# AstroEQ_PTH_V4_7.net
KiCad netlist of a schematic drawn in EAGLE
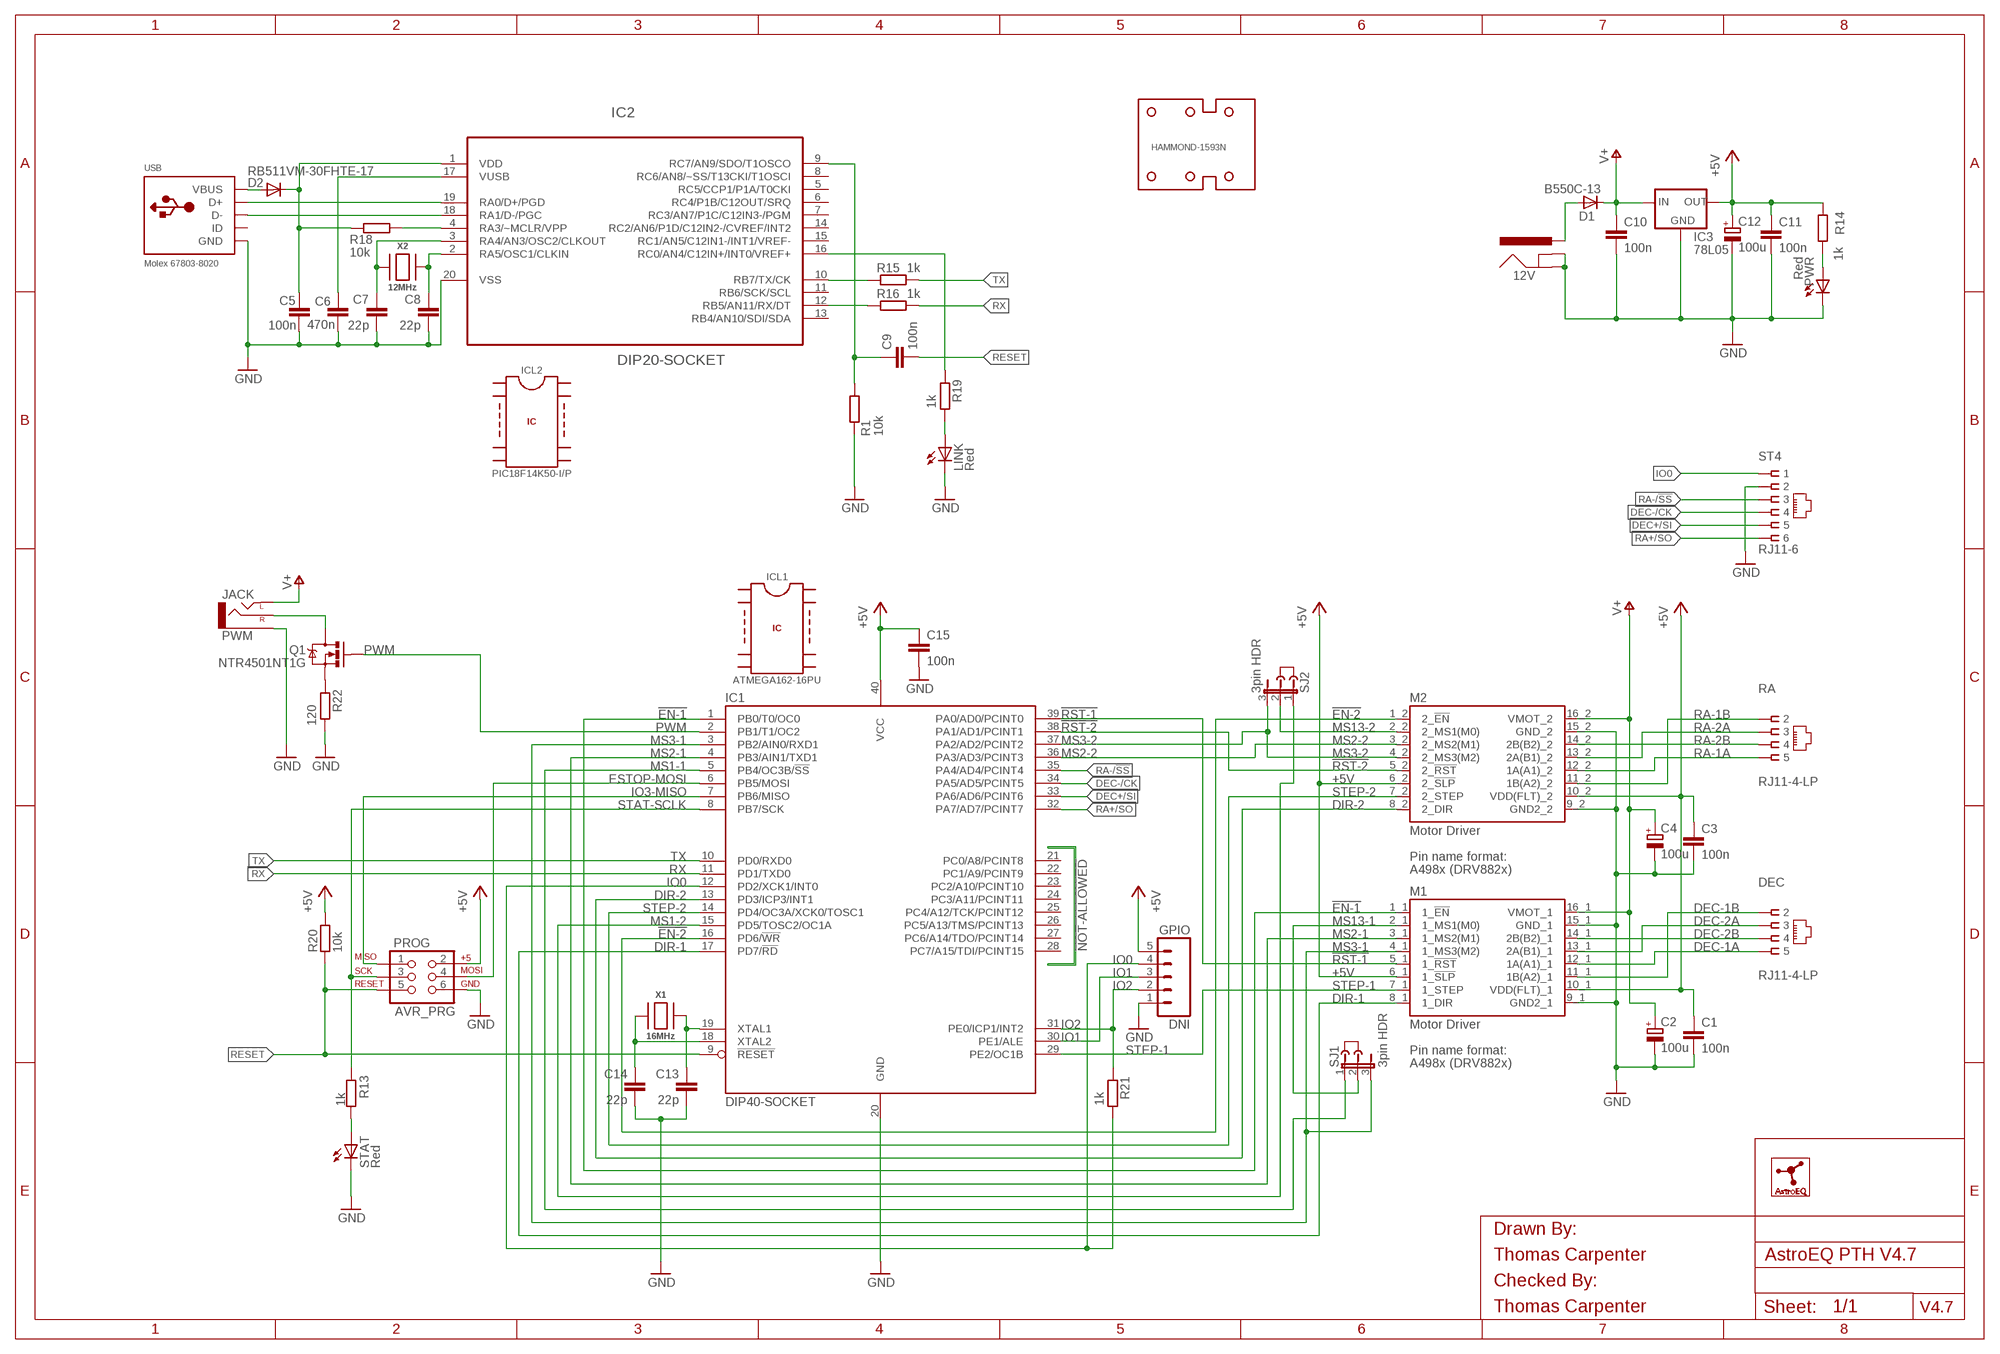
[diagram p0: schematic, sheet 1]

(export (version "E")
  (design (tool "Eeschema 10.0.6"))
  (components
    (comp (ref "12V")
      (value "POWER_JACKPTH")
      (footprint "eagle-import:POWER_JACK_PTH")
      (fields (field (name "MF") "MULTICOMP") (field (name "MPN") "MJ-179PH"))
      (libsource (lib "eagle-import") (part "POWER_JACKPTH"))
    )
    (comp (ref "C1")
      (value "100n")
      (footprint "eagle-import:C0603")
      (fields (field (name "MF") "MULTICOMP") (field (name "MPN") "MC0603F104Z250CT"))
      (libsource (lib "eagle-import") (part "C-EUC0603"))
    )
    (comp (ref "C2")
      (value "100u")
      (footprint "eagle-import:PANASONIC_D")
      (fields (field (name "MF") "WURTH ELEKTRONIK") (field (name "MPN") "865080545012"))
      (libsource (lib "eagle-import") (part "CPOL-EUD"))
    )
    (comp (ref "C3")
      (value "100n")
      (footprint "eagle-import:C0603")
      (fields (field (name "MF") "MULTICOMP") (field (name "MPN") "MC0603F104Z250CT"))
      (libsource (lib "eagle-import") (part "C-EUC0603"))
    )
    (comp (ref "C4")
      (value "100u")
      (footprint "eagle-import:PANASONIC_D")
      (fields (field (name "MF") "WURTH ELEKTRONIK") (field (name "MPN") "865080545012"))
      (libsource (lib "eagle-import") (part "CPOL-EUD"))
    )
    (comp (ref "C5")
      (value "100n")
      (footprint "eagle-import:C0603")
      (fields (field (name "MF") "MULTICOMP") (field (name "MPN") "MC0603F104Z250CT"))
      (libsource (lib "eagle-import") (part "C-EUC0603"))
    )
    (comp (ref "C6")
      (value "470n")
      (footprint "eagle-import:C0603")
      (fields (field (name "MF") "MULTICOMP") (field (name "MPN") "MC0603F474Z160CT"))
      (libsource (lib "eagle-import") (part "C-EUC0603"))
    )
    (comp (ref "C7")
      (value "22p")
      (footprint "eagle-import:C0603")
      (fields (field (name "MF") "MULTICOMP") (field (name "MPN") "MC0603N220J500CT"))
      (libsource (lib "eagle-import") (part "C-EUC0603"))
    )
    (comp (ref "C8")
      (value "22p")
      (footprint "eagle-import:C0603")
      (fields (field (name "MF") "MULTICOMP") (field (name "MPN") "MC0603N220J500CT"))
      (libsource (lib "eagle-import") (part "C-EUC0603"))
    )
    (comp (ref "C9")
      (value "100n")
      (footprint "eagle-import:C0603")
      (fields (field (name "MF") "MULTICOMP") (field (name "MPN") "MC0603F104Z250CT"))
      (libsource (lib "eagle-import") (part "C-EUC0603"))
    )
    (comp (ref "C10")
      (value "100n")
      (footprint "eagle-import:C0603")
      (fields (field (name "MF") "MULTICOMP") (field (name "MPN") "MC0603F104Z250CT"))
      (libsource (lib "eagle-import") (part "C-EUC0603"))
    )
    (comp (ref "C11")
      (value "100n")
      (footprint "eagle-import:C0603")
      (fields (field (name "MF") "MULTICOMP") (field (name "MPN") "MC0603F104Z250CT"))
      (libsource (lib "eagle-import") (part "C-EUC0603"))
    )
    (comp (ref "C12")
      (value "100u")
      (footprint "eagle-import:PANASONIC_D")
      (fields (field (name "MF") "WURTH ELEKTRONIK") (field (name "MPN") "865080545012"))
      (libsource (lib "eagle-import") (part "CPOL-EUD"))
    )
    (comp (ref "C13")
      (value "22p")
      (footprint "eagle-import:C0603")
      (fields (field (name "MF") "MULTICOMP") (field (name "MPN") "MC0603N220J500CT"))
      (libsource (lib "eagle-import") (part "C-EUC0603"))
    )
    (comp (ref "C14")
      (value "22p")
      (footprint "eagle-import:C0603")
      (fields (field (name "MF") "MULTICOMP") (field (name "MPN") "MC0603N220J500CT"))
      (libsource (lib "eagle-import") (part "C-EUC0603"))
    )
    (comp (ref "C15")
      (value "100n")
      (footprint "eagle-import:C0603")
      (fields (field (name "MF") "MULTICOMP") (field (name "MPN") "MC0603F104Z250CT"))
      (libsource (lib "eagle-import") (part "C-EUC0603"))
    )
    (comp (ref "D1")
      (value "B550C-13")
      (footprint "eagle-import:SMC")
      (fields (field (name "MF") "DIODES INC.") (field (name "MPN") "B550C-13-F"))
      (libsource (lib "eagle-import") (part "DIODE-SMC"))
    )
    (comp (ref "D2")
      (value "RB511VM-30FHTE-17")
      (footprint "eagle-import:SOD-323")
      (fields (field (name "MF") "ROHM"))
      (libsource (lib "eagle-import") (part "DIODESOD"))
    )
    (comp (ref "DEC")
      (value "RJ11-4-LP")
      (footprint "eagle-import:RJ11-NO_SHIELD-4-LP")
      (fields (field (name "MF") "MOLEX") (field (name "MPN") "95501-2641"))
      (libsource (lib "eagle-import") (part "RJ11-4-LP"))
    )
    (comp (ref "GPIO")
      (value "DNI")
      (footprint "eagle-import:1X05")
      (libsource (lib "eagle-import") (part "M05PTH"))
    )
    (comp (ref "HAMMOND-1593N")
      (value "HAMMOND-1593N-4HOLE")
      (footprint "eagle-import:HAMMOND-1593N4HOLES")
      (fields (field (name "MF") "HAMMOND") (field (name "MPN") "1593NBK"))
      (libsource (lib "eagle-import") (part "HAMMOND-1593N-4HOLE"))
    )
    (comp (ref "IC1")
      (value "DIP40-SOCKET")
      (footprint "eagle-import:DIL40")
      (fields (field (name "MF") "MULTICOMP") (field (name "MPN") "2227MC-40-06-05-F1"))
      (libsource (lib "eagle-import") (part "ATMEGA162-16PU"))
    )
    (comp (ref "IC2")
      (value "DIP20-SOCKET")
      (footprint "eagle-import:DIL20-SKT")
      (fields (field (name "MF") "MULTICOMP"))
      (libsource (lib "eagle-import") (part "PIC18F14K50/P-SKT-I"))
    )
    (comp (ref "IC3")
      (value "78L05")
      (footprint "eagle-import:SOT89")
      (fields (field (name "MF") "STMICROELECTRONICS") (field (name "MPN") "L78L05ACUTR"))
      (libsource (lib "eagle-import") (part "V_REG_78XX-SOT89"))
    )
    (comp (ref "ICL1")
      (value "ATMEGA162-16PU")
      (footprint "eagle-import:IC")
      (fields (field (name "MF") "ATMEL"))
      (libsource (lib "eagle-import") (part "IC"))
    )
    (comp (ref "ICL2")
      (value "PIC18F14K50-I/P")
      (footprint "eagle-import:IC")
      (fields (field (name "MF") "MICROCHIP"))
      (libsource (lib "eagle-import") (part "IC"))
    )
    (comp (ref "J2")
      (value "DNI")
      (footprint "eagle-import:JUMP")
      (fields (field (name "MF") "3M") (field (name "MPN") "969102-0000-DA"))
      (libsource (lib "eagle-import") (part "JUMPER"))
    )
    (comp (ref "J3")
      (value "DNI")
      (footprint "eagle-import:JUMP")
      (fields (field (name "MF") "3M") (field (name "MPN") "969102-0000-DA"))
      (libsource (lib "eagle-import") (part "JUMPER"))
    )
    (comp (ref "LINK")
      (value "Red")
      (footprint "eagle-import:SML1206-SIDE")
      (fields (field (name "MF") "WURTH ELEKTRONIK") (field (name "MPN") "155124RS73200"))
      (libsource (lib "eagle-import") (part "LED-1206-SIDE"))
    )
    (comp (ref "LOGO1")
      (value "DNI")
      (footprint "eagle-import:ASTROEQ-SMALL")
      (libsource (lib "eagle-import") (part "ASTROEQ5MM"))
    )
    (comp (ref "M1")
      (value "Motor Driver")
      (footprint "eagle-import:CARRIER-HV-DUAL")
      (fields (field (name "MF") "SAMTEC") (field (name "MPN") "CES-116-01-T-S"))
      (libsource (lib "eagle-import") (part "A4983-DUAL-HV"))
    )
    (comp (ref "M2")
      (value "Motor Driver")
      (footprint "eagle-import:CARRIER-LV-DUAL")
      (fields (field (name "MF") "SAMTEC") (field (name "MPN") "CES-116-01-T-S"))
      (libsource (lib "eagle-import") (part "A4983-DUAL-LV"))
    )
    (comp (ref "PROG")
      (value "AVR_PRG")
      (footprint "eagle-import:2X3")
      (fields (field (name "MF") "HARWIN") (field (name "MPN") "M20-9980346"))
      (libsource (lib "eagle-import") (part "AVR_SPI_PRG_6PTH"))
    )
    (comp (ref "PWM")
      (value "JACK")
      (footprint "eagle-import:AUDIO-JACK")
      (fields (field (name "MF") "CLIFF ELECTRONIC COMPONENTS") (field (name "MPN") "FC68131"))
      (libsource (lib "eagle-import") (part "AUDIO-JACKPTH"))
    )
    (comp (ref "PWR")
      (value "Red")
      (footprint "eagle-import:SML1206-SIDE")
      (fields (field (name "MF") "WURTH ELEKTRONIK") (field (name "MPN") "155124RS73200"))
      (libsource (lib "eagle-import") (part "LED-1206-SIDE"))
    )
    (comp (ref "Q1")
      (value "NTR4501NT1G")
      (footprint "eagle-import:SOT23-3")
      (fields (field (name "MF") "ON SEMICONDUCTOR"))
      (libsource (lib "eagle-import") (part "MOSFET-NCHANNELSMD"))
    )
    (comp (ref "R1")
      (value "10k")
      (footprint "eagle-import:R0603")
      (fields (field (name "MF") "MULTICOMP") (field (name "MPN") "MCWR06X1002FTL"))
      (libsource (lib "eagle-import") (part "R-EU_R0603"))
    )
    (comp (ref "R13")
      (value "1k")
      (footprint "eagle-import:R0603")
      (fields (field (name "MF") "MULTICOMP") (field (name "MPN") "MCWR06X1001FTL"))
      (libsource (lib "eagle-import") (part "R-EU_R0603"))
    )
    (comp (ref "R14")
      (value "1k")
      (footprint "eagle-import:R0603")
      (fields (field (name "MF") "MULTICOMP") (field (name "MPN") "MCWR06X1001FTL"))
      (libsource (lib "eagle-import") (part "R-EU_R0603"))
    )
    (comp (ref "R15")
      (value "1k")
      (footprint "eagle-import:R0603")
      (fields (field (name "MF") "MULTICOMP") (field (name "MPN") "MCWR06X1001FTL"))
      (libsource (lib "eagle-import") (part "R-EU_R0603"))
    )
    (comp (ref "R16")
      (value "1k")
      (footprint "eagle-import:R0603")
      (fields (field (name "MF") "MULTICOMP") (field (name "MPN") "MCWR06X1001FTL"))
      (libsource (lib "eagle-import") (part "R-EU_R0603"))
    )
    (comp (ref "R18")
      (value "10k")
      (footprint "eagle-import:R0603")
      (fields (field (name "MF") "MULTICOMP") (field (name "MPN") "MCWR06X1002FTL"))
      (libsource (lib "eagle-import") (part "R-EU_R0603"))
    )
    (comp (ref "R19")
      (value "1k")
      (footprint "eagle-import:R0603")
      (fields (field (name "MF") "MULTICOMP") (field (name "MPN") "MCWR06X1001FTL"))
      (libsource (lib "eagle-import") (part "R-EU_R0603"))
    )
    (comp (ref "R20")
      (value "10k")
      (footprint "eagle-import:R0603")
      (fields (field (name "MF") "MULTICOMP") (field (name "MPN") "MCWR06X1002FTL"))
      (libsource (lib "eagle-import") (part "R-EU_R0603"))
    )
    (comp (ref "R21")
      (value "1k")
      (footprint "eagle-import:R0603")
      (fields (field (name "MF") "MULTICOMP") (field (name "MPN") "MCWR06X1001FTL"))
      (libsource (lib "eagle-import") (part "R-EU_R0603"))
    )
    (comp (ref "R22")
      (value "120")
      (footprint "eagle-import:R0805")
      (fields (field (name "MF") "MULTICOMP") (field (name "MPN") "MCWR08X1200FTL"))
      (libsource (lib "eagle-import") (part "R-EU_R0805"))
    )
    (comp (ref "RA")
      (value "RJ11-4-LP")
      (footprint "eagle-import:RJ11-NO_SHIELD-4-LP")
      (fields (field (name "MF") "MOLEX") (field (name "MPN") "95501-2641"))
      (libsource (lib "eagle-import") (part "RJ11-4-LP"))
    )
    (comp (ref "SJ1")
      (value "3pin HDR")
      (footprint "eagle-import:JP2")
      (fields (field (name "MF") "HARWIN") (field (name "MPN") "M20-9990345."))
      (libsource (lib "eagle-import") (part "JP2E"))
    )
    (comp (ref "SJ2")
      (value "3pin HDR")
      (footprint "eagle-import:JP2")
      (fields (field (name "MF") "HARWIN") (field (name "MPN") "M20-9990345."))
      (libsource (lib "eagle-import") (part "JP2E"))
    )
    (comp (ref "ST4")
      (value "RJ11-6")
      (footprint "eagle-import:RJ11-NO_SHIELD-LP")
      (fields (field (name "MF") "MOLEX") (field (name "MPN") "95501-2661"))
      (libsource (lib "eagle-import") (part "RJ11-LP"))
    )
    (comp (ref "STAT")
      (value "Red")
      (footprint "eagle-import:SML1206-SIDE")
      (fields (field (name "MF") "WURTH ELEKTRONIK") (field (name "MPN") "155124RS73200"))
      (libsource (lib "eagle-import") (part "LED-1206-SIDE"))
    )
    (comp (ref "USB")
      (value "Molex 67803-8020")
      (footprint "eagle-import:USB-MINIAB")
      (fields (field (name "MF") "MOLEX") (field (name "MPN") "67803-8020"))
      (libsource (lib "eagle-import") (part "USBMINIAB"))
    )
    (comp (ref "X1")
      (value "16MHz")
      (footprint "eagle-import:NX5032")
      (fields (field (name "MF") "TXC") (field (name "MPN") "7A-16.000MAAJ-T"))
      (libsource (lib "eagle-import") (part "XTALNX5032"))
    )
    (comp (ref "X2")
      (value "12MHz")
      (footprint "eagle-import:NX5032")
      (fields (field (name "MF") "TXC") (field (name "MPN") "7A-12.000MAAJ-T"))
      (libsource (lib "eagle-import") (part "XTALNX5032"))
    )
  )
  (nets
    (net (code "1") (name "+5V") (class "Default")
      (node (ref "C1") (pin "1") (pinfunction "1_1") (pintype "passive"))
      (node (ref "C11") (pin "1") (pinfunction "1_1") (pintype "passive"))
      (node (ref "C12") (pin "+") (pinfunction "+_+") (pintype "passive"))
      (node (ref "C15") (pin "1") (pinfunction "1_1") (pintype "passive"))
      (node (ref "C3") (pin "1") (pinfunction "1_1") (pintype "passive"))
      (node (ref "GPIO") (pin "5") (pinfunction "5_5") (pintype "passive"))
      (node (ref "IC1") (pin "40") (pinfunction "VCC_40") (pintype "power_in"))
      (node (ref "IC3") (pin "1") (pinfunction "OUT_1") (pintype "power_in"))
      (node (ref "M1") (pin "10_1") (pinfunction "VDD(FLT)_1_10_1") (pintype "power_in"))
      (node (ref "M1") (pin "10_2") (pinfunction "VDD(FLT)_2_10_2") (pintype "power_in"))
      (node (ref "M2") (pin "6_1") (pinfunction "1_~{SLP}_6_1") (pintype "input"))
      (node (ref "M2") (pin "6_2") (pinfunction "2_~{SLP}_6_2") (pintype "input"))
      (node (ref "PROG") (pin "2") (pinfunction "2_2") (pintype "passive"))
      (node (ref "R14") (pin "1") (pinfunction "1_1") (pintype "passive"))
      (node (ref "R20") (pin "2") (pinfunction "2_2") (pintype "passive"))
    )
    (net (code "2") (name "/DEC-1A") (class "Default")
      (node (ref "DEC") (pin "5") (pinfunction "5_5") (pintype "passive"))
      (node (ref "M1") (pin "12_1") (pinfunction "1A(A1)_1_12_1") (pintype "output"))
    )
    (net (code "3") (name "/DEC-1B") (class "Default")
      (node (ref "DEC") (pin "2") (pinfunction "2_2") (pintype "passive"))
      (node (ref "M1") (pin "11_1") (pinfunction "1B(A2)_1_11_1") (pintype "output"))
    )
    (net (code "4") (name "/DEC-2A") (class "Default")
      (node (ref "DEC") (pin "3") (pinfunction "3_3") (pintype "passive"))
      (node (ref "M1") (pin "13_1") (pinfunction "2A(B1)_1_13_1") (pintype "output"))
    )
    (net (code "5") (name "/DEC-2B") (class "Default")
      (node (ref "DEC") (pin "4") (pinfunction "4_4") (pintype "passive"))
      (node (ref "M1") (pin "14_1") (pinfunction "2B(B2)_1_14_1") (pintype "output"))
    )
    (net (code "6") (name "/DIR-1") (class "Default")
      (node (ref "IC1") (pin "17") (pinfunction "PD7/~{RD}_17") (pintype "bidirectional"))
      (node (ref "M2") (pin "8_1") (pinfunction "1_DIR_8_1") (pintype "input"))
    )
    (net (code "7") (name "/DIR-2") (class "Default")
      (node (ref "IC1") (pin "13") (pinfunction "PD3/ICP3/INT1_13") (pintype "bidirectional"))
      (node (ref "M2") (pin "8_2") (pinfunction "2_DIR_8_2") (pintype "input"))
    )
    (net (code "8") (name "/ESTOP-MOSI") (class "Default")
      (node (ref "IC1") (pin "6") (pinfunction "PB5/MOSI_6") (pintype "bidirectional"))
      (node (ref "PROG") (pin "4") (pinfunction "4_4") (pintype "passive"))
    )
    (net (code "9") (name "/IO1") (class "Default")
      (node (ref "GPIO") (pin "3") (pinfunction "3_3") (pintype "passive"))
      (node (ref "IC1") (pin "30") (pinfunction "PE1/ALE_30") (pintype "bidirectional"))
    )
    (net (code "10") (name "/IO2") (class "Default")
      (node (ref "GPIO") (pin "2") (pinfunction "2_2") (pintype "passive"))
      (node (ref "IC1") (pin "31") (pinfunction "PE0/ICP1/INT2_31") (pintype "bidirectional"))
      (node (ref "R21") (pin "2") (pinfunction "2_2") (pintype "passive"))
    )
    (net (code "11") (name "/IO3-MISO") (class "Default")
      (node (ref "IC1") (pin "7") (pinfunction "PB6/MISO_7") (pintype "bidirectional"))
      (node (ref "PROG") (pin "1") (pinfunction "1_1") (pintype "passive"))
    )
    (net (code "12") (name "/MS1-1") (class "Default")
      (node (ref "IC1") (pin "5") (pinfunction "PB4/OC3B/~{SS}_5") (pintype "bidirectional"))
      (node (ref "SJ1") (pin "1") (pinfunction "1_1") (pintype "passive"))
    )
    (net (code "13") (name "/MS1-2") (class "Default")
      (node (ref "IC1") (pin "15") (pinfunction "PD5/TOSC2/OC1A_15") (pintype "bidirectional"))
      (node (ref "SJ2") (pin "1") (pinfunction "1_1") (pintype "passive"))
    )
    (net (code "14") (name "/MS2-1") (class "Default")
      (node (ref "IC1") (pin "4") (pinfunction "PB3/AIN1/TXD1_4") (pintype "bidirectional"))
      (node (ref "M2") (pin "3_1") (pinfunction "1_MS2(M1)_3_1") (pintype "input"))
    )
    (net (code "15") (name "/MS2-2") (class "Default")
      (node (ref "IC1") (pin "36") (pinfunction "PA3/AD3/PCINT3_36") (pintype "bidirectional"))
      (node (ref "M2") (pin "3_2") (pinfunction "2_MS2(M1)_3_2") (pintype "input"))
    )
    (net (code "16") (name "/MS3-1") (class "Default")
      (node (ref "IC1") (pin "3") (pinfunction "PB2/AIN0/RXD1_3") (pintype "bidirectional"))
      (node (ref "M2") (pin "4_1") (pinfunction "1_MS3(M2)_4_1") (pintype "input"))
      (node (ref "SJ1") (pin "3") (pinfunction "3_3") (pintype "passive"))
    )
    (net (code "17") (name "/MS3-2") (class "Default")
      (node (ref "IC1") (pin "37") (pinfunction "PA2/AD2/PCINT2_37") (pintype "bidirectional"))
      (node (ref "M2") (pin "4_2") (pinfunction "2_MS3(M2)_4_2") (pintype "input"))
      (node (ref "SJ2") (pin "3") (pinfunction "3_3") (pintype "passive"))
    )
    (net (code "18") (name "/MS13-1") (class "Default")
      (node (ref "M2") (pin "2_1") (pinfunction "1_MS1(M0)_2_1") (pintype "input"))
      (node (ref "SJ1") (pin "2") (pinfunction "2_2") (pintype "passive"))
    )
    (net (code "19") (name "/MS13-2") (class "Default")
      (node (ref "M2") (pin "2_2") (pinfunction "2_MS1(M0)_2_2") (pintype "input"))
      (node (ref "SJ2") (pin "2") (pinfunction "2_2") (pintype "passive"))
    )
    (net (code "20") (name "/PWM") (class "Default")
      (node (ref "IC1") (pin "2") (pinfunction "PB1/T1/OC2_2") (pintype "bidirectional"))
      (node (ref "Q1") (pin "1") (pinfunction "G_1") (pintype "passive"))
    )
    (net (code "21") (name "/RA-1A") (class "Default")
      (node (ref "M1") (pin "12_2") (pinfunction "1A(A1)_2_12_2") (pintype "output"))
      (node (ref "RA") (pin "5") (pinfunction "5_5") (pintype "passive"))
    )
    (net (code "22") (name "/RA-1B") (class "Default")
      (node (ref "M1") (pin "11_2") (pinfunction "1B(A2)_2_11_2") (pintype "output"))
      (node (ref "RA") (pin "2") (pinfunction "2_2") (pintype "passive"))
    )
    (net (code "23") (name "/RA-2A") (class "Default")
      (node (ref "M1") (pin "13_2") (pinfunction "2A(B1)_2_13_2") (pintype "output"))
      (node (ref "RA") (pin "3") (pinfunction "3_3") (pintype "passive"))
    )
    (net (code "24") (name "/RA-2B") (class "Default")
      (node (ref "M1") (pin "14_2") (pinfunction "2B(B2)_2_14_2") (pintype "output"))
      (node (ref "RA") (pin "4") (pinfunction "4_4") (pintype "passive"))
    )
    (net (code "25") (name "/RA-{slash}~{SS}") (class "Default")
      (node (ref "IC1") (pin "35") (pinfunction "PA4/AD4/PCINT4_35") (pintype "bidirectional"))
      (node (ref "ST4") (pin "3") (pinfunction "3_3") (pintype "passive"))
    )
    (net (code "26") (name "/STAT-SCLK") (class "Default")
      (node (ref "IC1") (pin "8") (pinfunction "PB7/SCK_8") (pintype "bidirectional"))
      (node (ref "PROG") (pin "3") (pinfunction "3_3") (pintype "passive"))
      (node (ref "R13") (pin "1") (pinfunction "1_1") (pintype "passive"))
    )
    (net (code "27") (name "/STEP-1") (class "Default")
      (node (ref "IC1") (pin "29") (pinfunction "PE2/OC1B_29") (pintype "bidirectional"))
      (node (ref "M2") (pin "7_1") (pinfunction "1_STEP_7_1") (pintype "input"))
    )
    (net (code "28") (name "/STEP-2") (class "Default")
      (node (ref "IC1") (pin "14") (pinfunction "PD4/OC3A/XCK0/TOSC1_14") (pintype "bidirectional"))
      (node (ref "M2") (pin "7_2") (pinfunction "2_STEP_7_2") (pintype "input"))
    )
    (net (code "29") (name "/~{EN-1}") (class "Default")
      (node (ref "IC1") (pin "1") (pinfunction "PB0/T0/OC0_1") (pintype "bidirectional"))
      (node (ref "M2") (pin "1_1") (pinfunction "1_~{EN}_1_1") (pintype "input"))
    )
    (net (code "30") (name "/~{EN-2}") (class "Default")
      (node (ref "IC1") (pin "16") (pinfunction "PD6/~{WR}_16") (pintype "bidirectional"))
      (node (ref "M2") (pin "1_2") (pinfunction "2_~{EN}_1_2") (pintype "input"))
    )
    (net (code "32") (name "/~{RST-1}") (class "Default")
      (node (ref "IC1") (pin "39") (pinfunction "PA0/AD0/PCINT0_39") (pintype "bidirectional"))
      (node (ref "M2") (pin "5_1") (pinfunction "1_~{RST}_5_1") (pintype "input"))
    )
    (net (code "33") (name "/~{RST-2}") (class "Default")
      (node (ref "IC1") (pin "38") (pinfunction "PA1/AD1/PCINT1_38") (pintype "bidirectional"))
      (node (ref "M2") (pin "5_2") (pinfunction "2_~{RST}_5_2") (pintype "input"))
    )
    (net (code "34") (name "DEC+{slash}SI") (class "Default")
      (node (ref "IC1") (pin "33") (pinfunction "PA6/AD6/PCINT6_33") (pintype "bidirectional"))
      (node (ref "ST4") (pin "5") (pinfunction "5_5") (pintype "passive"))
    )
    (net (code "35") (name "DEC-{slash}CK") (class "Default")
      (node (ref "IC1") (pin "34") (pinfunction "PA5/AD5/PCINT5_34") (pintype "bidirectional"))
      (node (ref "ST4") (pin "4") (pinfunction "4_4") (pintype "passive"))
    )
    (net (code "36") (name "GND") (class "Default")
      (node (ref "12V") (pin "GND") (pinfunction "GND_GND") (pintype "bidirectional"))
      (node (ref "12V") (pin "GNDBREAK") (pinfunction "GNDBREAK_GNDBREAK") (pintype "bidirectional"))
      (node (ref "C1") (pin "2") (pinfunction "2_2") (pintype "passive"))
      (node (ref "C10") (pin "2") (pinfunction "2_2") (pintype "passive"))
      (node (ref "C11") (pin "2") (pinfunction "2_2") (pintype "passive"))
      (node (ref "C12") (pin "-") (pinfunction "-_-") (pintype "passive"))
      (node (ref "C13") (pin "2") (pinfunction "2_2") (pintype "passive"))
      (node (ref "C14") (pin "2") (pinfunction "2_2") (pintype "passive"))
      (node (ref "C15") (pin "2") (pinfunction "2_2") (pintype "passive"))
      (node (ref "C2") (pin "-") (pinfunction "-_-") (pintype "passive"))
      (node (ref "C3") (pin "2") (pinfunction "2_2") (pintype "passive"))
      (node (ref "C4") (pin "-") (pinfunction "-_-") (pintype "passive"))
      (node (ref "C5") (pin "2") (pinfunction "2_2") (pintype "passive"))
      (node (ref "C6") (pin "1") (pinfunction "1_1") (pintype "passive"))
      (node (ref "C7") (pin "2") (pinfunction "2_2") (pintype "passive"))
      (node (ref "C8") (pin "2") (pinfunction "2_2") (pintype "passive"))
      (node (ref "GPIO") (pin "1") (pinfunction "1_1") (pintype "passive"))
      (node (ref "IC1") (pin "20") (pinfunction "GND_20") (pintype "power_in"))
      (node (ref "IC2") (pin "20") (pinfunction "VSS_20") (pintype "power_in"))
      (node (ref "IC3") (pin "2") (pinfunction "GND_2") (pintype "power_in"))
      (node (ref "IC3") (pin "4") (pinfunction "GND_4") (pintype "power_in"))
      (node (ref "LINK") (pin "C") (pinfunction "C_C") (pintype "passive"))
      (node (ref "LINK") (pin "E") (pinfunction "C_E") (pintype "passive"))
      (node (ref "M1") (pin "15_1") (pinfunction "GND_1_15_1") (pintype "power_in"))
      (node (ref "M1") (pin "15_2") (pinfunction "GND_2_15_2") (pintype "power_in"))
      (node (ref "M1") (pin "9_1") (pinfunction "GND2_1_9_1") (pintype "power_in"))
      (node (ref "M1") (pin "9_2") (pinfunction "GND2_2_9_2") (pintype "power_in"))
      (node (ref "PROG") (pin "6") (pinfunction "6_6") (pintype "passive"))
      (node (ref "PWM") (pin "SLEEVE") (pinfunction "SLEEVE_SLEEVE") (pintype "bidirectional"))
      (node (ref "PWR") (pin "C") (pinfunction "C_C") (pintype "passive"))
      (node (ref "PWR") (pin "E") (pinfunction "C_E") (pintype "passive"))
      (node (ref "R1") (pin "2") (pinfunction "2_2") (pintype "passive"))
      (node (ref "R22") (pin "1") (pinfunction "1_1") (pintype "passive"))
      (node (ref "ST4") (pin "2") (pinfunction "2_2") (pintype "passive"))
      (node (ref "STAT") (pin "C") (pinfunction "C_C") (pintype "passive"))
      (node (ref "STAT") (pin "E") (pinfunction "C_E") (pintype "passive"))
      (node (ref "USB") (pin "GND") (pinfunction "GND_GND") (pintype "power_in"))
      (node (ref "USB") (pin "GND1") (pinfunction "GND_GND1") (pintype "power_in"))
      (node (ref "USB") (pin "GND2") (pinfunction "GND_GND2") (pintype "power_in"))
      (node (ref "USB") (pin "GND3") (pinfunction "GND_GND3") (pintype "power_in"))
      (node (ref "USB") (pin "GND4") (pinfunction "GND_GND4") (pintype "power_in"))
    )
    (net (code "37") (name "IO0") (class "Default")
      (node (ref "GPIO") (pin "4") (pinfunction "4_4") (pintype "passive"))
      (node (ref "IC1") (pin "12") (pinfunction "PD2/XCK1/INT0_12") (pintype "bidirectional"))
      (node (ref "R21") (pin "1") (pinfunction "1_1") (pintype "passive"))
      (node (ref "ST4") (pin "1") (pinfunction "1_1") (pintype "passive"))
    )
    (net (code "38") (name "Net-(12V-PadPWR)") (class "Default")
      (node (ref "12V") (pin "PWR") (pinfunction "PWR_PWR") (pintype "bidirectional"))
      (node (ref "D1") (pin "A") (pinfunction "A_A") (pintype "passive"))
    )
    (net (code "39") (name "Net-(D2-A)") (class "Default")
      (node (ref "D2") (pin "2") (pinfunction "A_2") (pintype "passive"))
      (node (ref "USB") (pin "VBUS") (pinfunction "VBUS_VBUS") (pintype "power_in"))
    )
    (net (code "40") (name "Net-(D2-C)") (class "Default")
      (node (ref "C5") (pin "1") (pinfunction "1_1") (pintype "passive"))
      (node (ref "D2") (pin "1") (pinfunction "C_1") (pintype "passive"))
      (node (ref "IC2") (pin "1") (pinfunction "VDD_1") (pintype "power_in"))
      (node (ref "R18") (pin "2") (pinfunction "2_2") (pintype "passive"))
    )
    (net (code "41") (name "Net-(IC1-XTAL1)") (class "Default")
      (node (ref "C13") (pin "1") (pinfunction "1_1") (pintype "passive"))
      (node (ref "IC1") (pin "19") (pinfunction "XTAL1_19") (pintype "input"))
      (node (ref "X1") (pin "P$2") (pinfunction "P$2_P$2") (pintype "bidirectional"))
    )
    (net (code "42") (name "Net-(IC1-XTAL2)") (class "Default")
      (node (ref "C14") (pin "1") (pinfunction "1_1") (pintype "passive"))
      (node (ref "IC1") (pin "18") (pinfunction "XTAL2_18") (pintype "input"))
      (node (ref "X1") (pin "P$1") (pinfunction "P$1_P$1") (pintype "bidirectional"))
    )
    (net (code "43") (name "Net-(IC2-RA0{slash}D+{slash}PGD)") (class "Default")
      (node (ref "IC2") (pin "19") (pinfunction "RA0/D+/PGD_19") (pintype "bidirectional"))
      (node (ref "USB") (pin "D+") (pinfunction "D+_D+") (pintype "bidirectional"))
    )
    (net (code "44") (name "Net-(IC2-RA1{slash}D-{slash}PGC)") (class "Default")
      (node (ref "IC2") (pin "18") (pinfunction "RA1/D-/PGC_18") (pintype "bidirectional"))
      (node (ref "USB") (pin "D-") (pinfunction "D-_D-") (pintype "bidirectional"))
    )
    (net (code "45") (name "Net-(IC2-RA3{slash}~{MCLR{slash}VPP})") (class "Default")
      (node (ref "IC2") (pin "4") (pinfunction "RA3/~{MCLR/VPP}_4") (pintype "input"))
      (node (ref "R18") (pin "1") (pinfunction "1_1") (pintype "passive"))
    )
    (net (code "46") (name "Net-(IC2-RA4{slash}AN3{slash}OSC2{slash}CLKOUT)") (class "Default")
      (node (ref "C7") (pin "1") (pinfunction "1_1") (pintype "passive"))
      (node (ref "IC2") (pin "3") (pinfunction "RA4/AN3/OSC2/CLKOUT_3") (pintype "bidirectional"))
      (node (ref "X2") (pin "P$1") (pinfunction "P$1_P$1") (pintype "bidirectional"))
    )
    (net (code "47") (name "Net-(IC2-RA5{slash}OSC1{slash}CLKIN)") (class "Default")
      (node (ref "C8") (pin "1") (pinfunction "1_1") (pintype "passive"))
      (node (ref "IC2") (pin "2") (pinfunction "RA5/OSC1/CLKIN_2") (pintype "bidirectional"))
      (node (ref "X2") (pin "P$2") (pinfunction "P$2_P$2") (pintype "bidirectional"))
    )
    (net (code "48") (name "Net-(IC2-RB5{slash}AN11{slash}RX{slash}DT)") (class "Default")
      (node (ref "IC2") (pin "12") (pinfunction "RB5/AN11/RX/DT_12") (pintype "bidirectional"))
      (node (ref "R16") (pin "2") (pinfunction "2_2") (pintype "passive"))
    )
    (net (code "49") (name "Net-(IC2-RB7{slash}TX{slash}CK)") (class "Default")
      (node (ref "IC2") (pin "10") (pinfunction "RB7/TX/CK_10") (pintype "bidirectional"))
      (node (ref "R15") (pin "2") (pinfunction "2_2") (pintype "passive"))
    )
    (net (code "50") (name "Net-(IC2-RC0{slash}AN4{slash}C12IN+{slash}INT0{slash}VREF+)") (class "Default")
      (node (ref "IC2") (pin "16") (pinfunction "RC0/AN4/C12IN+/INT0/VREF+_16") (pintype "bidirectional"))
      (node (ref "R19") (pin "2") (pinfunction "2_2") (pintype "passive"))
    )
    (net (code "51") (name "Net-(IC2-RC7{slash}AN9{slash}SDO{slash}T1OSCO)") (class "Default")
      (node (ref "C9") (pin "1") (pinfunction "1_1") (pintype "passive"))
      (node (ref "IC2") (pin "9") (pinfunction "RC7/AN9/SDO/T1OSCO_9") (pintype "bidirectional"))
      (node (ref "R1") (pin "1") (pinfunction "1_1") (pintype "passive"))
    )
    (net (code "52") (name "Net-(IC2-VUSB)") (class "Default")
      (node (ref "C6") (pin "2") (pinfunction "2_2") (pintype "passive"))
      (node (ref "IC2") (pin "17") (pinfunction "VUSB_17") (pintype "power_in"))
    )
    (net (code "53") (name "Net-(LINK-PadA)") (class "Default")
      (node (ref "LINK") (pin "A") (pinfunction "A_A") (pintype "passive"))
      (node (ref "R19") (pin "1") (pinfunction "1_1") (pintype "passive"))
    )
    (net (code "54") (name "Net-(PWM-RIGHT)") (class "Default")
      (node (ref "PWM") (pin "RING") (pinfunction "RIGHT_RING") (pintype "bidirectional"))
      (node (ref "Q1") (pin "3") (pinfunction "D_3") (pintype "passive"))
    )
    (net (code "55") (name "Net-(PWR-PadA)") (class "Default")
      (node (ref "PWR") (pin "A") (pinfunction "A_A") (pintype "passive"))
      (node (ref "R14") (pin "2") (pinfunction "2_2") (pintype "passive"))
    )
    (net (code "56") (name "Net-(Q1-S)") (class "Default")
      (node (ref "Q1") (pin "2") (pinfunction "S_2") (pintype "passive"))
      (node (ref "R22") (pin "2") (pinfunction "2_2") (pintype "passive"))
    )
    (net (code "57") (name "Net-(R13-Pad2)") (class "Default")
      (node (ref "R13") (pin "2") (pinfunction "2_2") (pintype "passive"))
      (node (ref "STAT") (pin "A") (pinfunction "A_A") (pintype "passive"))
    )
    (net (code "58") (name "RA+{slash}SO") (class "Default")
      (node (ref "IC1") (pin "32") (pinfunction "PA7/AD7/PCINT7_32") (pintype "bidirectional"))
      (node (ref "ST4") (pin "6") (pinfunction "6_6") (pintype "passive"))
    )
    (net (code "59") (name "RESET") (class "Default")
      (node (ref "C9") (pin "2") (pinfunction "2_2") (pintype "passive"))
      (node (ref "IC1") (pin "9") (pinfunction "~{RESET}_9") (pintype "input"))
      (node (ref "PROG") (pin "5") (pinfunction "5_5") (pintype "passive"))
      (node (ref "R20") (pin "1") (pinfunction "1_1") (pintype "passive"))
    )
    (net (code "60") (name "RX") (class "Default")
      (node (ref "IC1") (pin "11") (pinfunction "PD1/TXD0_11") (pintype "bidirectional"))
      (node (ref "R16") (pin "1") (pinfunction "1_1") (pintype "passive"))
    )
    (net (code "61") (name "TX") (class "Default")
      (node (ref "IC1") (pin "10") (pinfunction "PD0/RXD0_10") (pintype "bidirectional"))
      (node (ref "R15") (pin "1") (pinfunction "1_1") (pintype "passive"))
    )
    (net (code "62") (name "V+") (class "Default")
      (node (ref "C10") (pin "1") (pinfunction "1_1") (pintype "passive"))
      (node (ref "C2") (pin "+") (pinfunction "+_+") (pintype "passive"))
      (node (ref "C4") (pin "+") (pinfunction "+_+") (pintype "passive"))
      (node (ref "D1") (pin "C") (pinfunction "C_C") (pintype "passive"))
      (node (ref "IC3") (pin "3") (pinfunction "IN_3") (pintype "power_in"))
      (node (ref "M1") (pin "16_1") (pinfunction "VMOT_1_16_1") (pintype "power_in"))
      (node (ref "M1") (pin "16_2") (pinfunction "VMOT_2_16_2") (pintype "power_in"))
      (node (ref "PWM") (pin "TIP") (pinfunction "LEFT_TIP") (pintype "bidirectional"))
    )
    (net (code "63") (name "unconnected-(IC1-PC0{slash}A8{slash}PCINT8-Pad21)") (class "Default")
      (node (ref "IC1") (pin "21") (pinfunction "PC0/A8/PCINT8_21") (pintype "bidirectional"))
    )
    (net (code "64") (name "unconnected-(IC1-PC1{slash}A9{slash}PCINT9-Pad22)") (class "Default")
      (node (ref "IC1") (pin "22") (pinfunction "PC1/A9/PCINT9_22") (pintype "bidirectional"))
    )
    (net (code "65") (name "unconnected-(IC1-PC2{slash}A10{slash}PCINT10-Pad23)") (class "Default")
      (node (ref "IC1") (pin "23") (pinfunction "PC2/A10/PCINT10_23") (pintype "bidirectional"))
    )
    (net (code "66") (name "unconnected-(IC1-PC3{slash}A11{slash}PCINT11-Pad24)") (class "Default")
      (node (ref "IC1") (pin "24") (pinfunction "PC3/A11/PCINT11_24") (pintype "bidirectional"))
    )
    (net (code "67") (name "unconnected-(IC1-PC4{slash}A12{slash}TCK{slash}PCINT12-Pad25)") (class "Default")
      (node (ref "IC1") (pin "25") (pinfunction "PC4/A12/TCK/PCINT12_25") (pintype "bidirectional"))
    )
    (net (code "68") (name "unconnected-(IC1-PC5{slash}A13{slash}TMS{slash}PCINT13-Pad26)") (class "Default")
      (node (ref "IC1") (pin "26") (pinfunction "PC5/A13/TMS/PCINT13_26") (pintype "bidirectional"))
    )
    (net (code "69") (name "unconnected-(IC1-PC6{slash}A14{slash}TDO{slash}PCINT14-Pad27)") (class "Default")
      (node (ref "IC1") (pin "27") (pinfunction "PC6/A14/TDO/PCINT14_27") (pintype "bidirectional"))
    )
    (net (code "70") (name "unconnected-(IC1-PC7{slash}A15{slash}TDI{slash}PCINT15-Pad28)") (class "Default")
      (node (ref "IC1") (pin "28") (pinfunction "PC7/A15/TDI/PCINT15_28") (pintype "bidirectional"))
    )
    (net (code "71") (name "unconnected-(IC2-RB4{slash}AN10{slash}SDI{slash}SDA-Pad13)") (class "Default")
      (node (ref "IC2") (pin "13") (pinfunction "RB4/AN10/SDI/SDA_13") (pintype "bidirectional"))
    )
    (net (code "72") (name "unconnected-(IC2-RB6{slash}SCK{slash}SCL-Pad11)") (class "Default")
      (node (ref "IC2") (pin "11") (pinfunction "RB6/SCK/SCL_11") (pintype "bidirectional"))
    )
    (net (code "73") (name "unconnected-(IC2-RC1{slash}AN5{slash}C12IN1-{slash}INT1{slash}VREF--Pad15)") (class "Default")
      (node (ref "IC2") (pin "15") (pinfunction "RC1/AN5/C12IN1-/INT1/VREF-_15") (pintype "bidirectional"))
    )
    (net (code "74") (name "unconnected-(IC2-RC2{slash}AN6{slash}P1D{slash}C12IN2-{slash}CVREF{slash}INT2-Pad14)") (class "Default")
      (node (ref "IC2") (pin "14") (pinfunction "RC2/AN6/P1D/C12IN2-/CVREF/INT2_14") (pintype "bidirectional"))
    )
    (net (code "75") (name "unconnected-(IC2-RC3{slash}AN7{slash}P1C{slash}C12IN3-{slash}PGM-Pad7)") (class "Default")
      (node (ref "IC2") (pin "7") (pinfunction "RC3/AN7/P1C/C12IN3-/PGM_7") (pintype "bidirectional"))
    )
    (net (code "76") (name "unconnected-(IC2-RC4{slash}P1B{slash}C12OUT{slash}SRQ-Pad6)") (class "Default")
      (node (ref "IC2") (pin "6") (pinfunction "RC4/P1B/C12OUT/SRQ_6") (pintype "bidirectional"))
    )
    (net (code "77") (name "unconnected-(IC2-RC5{slash}CCP1{slash}P1A{slash}T0CKI-Pad5)") (class "Default")
      (node (ref "IC2") (pin "5") (pinfunction "RC5/CCP1/P1A/T0CKI_5") (pintype "bidirectional"))
    )
    (net (code "78") (name "unconnected-(IC2-RC6{slash}AN8{slash}~{SS{slash}T13CKI{slash}T1OSCI}-Pad8)") (class "Default")
      (node (ref "IC2") (pin "8") (pinfunction "RC6/AN8/~{SS/T13CKI/T1OSCI}_8") (pintype "bidirectional"))
    )
    (net (code "79") (name "unconnected-(USB-PadID)") (class "Default")
      (node (ref "USB") (pin "ID") (pinfunction "ID_ID") (pintype "bidirectional"))
    )
  )
)
